# midi2trigger.net
KiCad netlist of a schematic drawn in EAGLE
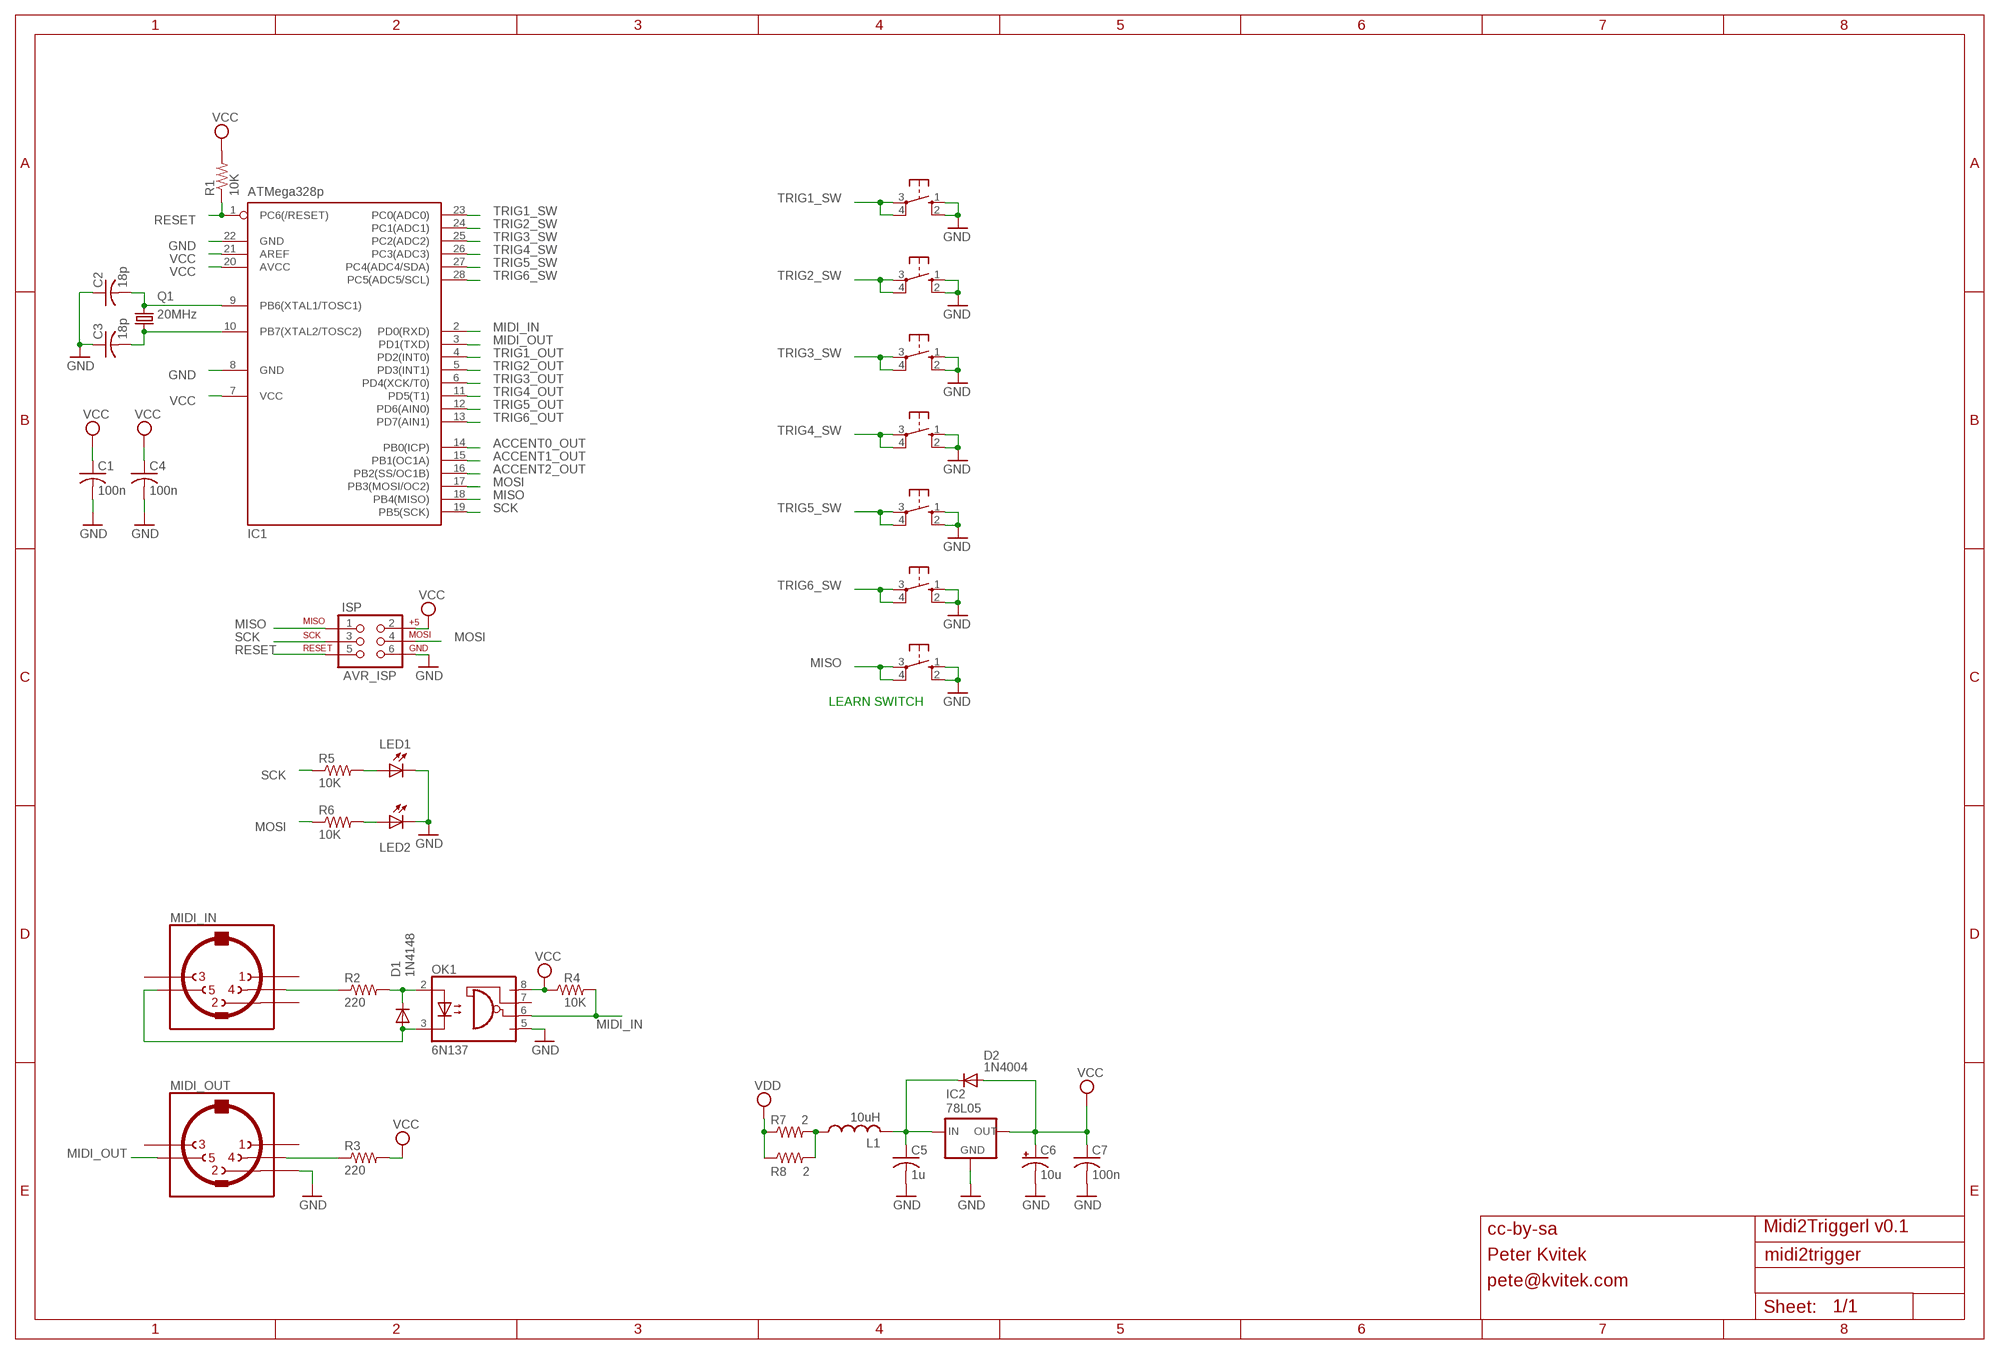
[diagram p0: schematic, sheet 1]

(export (version "E")
  (design (tool "Eeschema 10.0.6"))
  (components
    (comp (ref "C1")
      (value "100n")
      (footprint "eagle-import:C025-025X050")
      (libsource (lib "eagle-import") (part "C-US025-025X050"))
    )
    (comp (ref "C2")
      (value "18p")
      (footprint "eagle-import:C025-025X050")
      (libsource (lib "eagle-import") (part "C-US025-025X050"))
    )
    (comp (ref "C3")
      (value "18p")
      (footprint "eagle-import:C025-025X050")
      (libsource (lib "eagle-import") (part "C-US025-025X050"))
    )
    (comp (ref "C4")
      (value "100n")
      (footprint "eagle-import:C025-025X050")
      (libsource (lib "eagle-import") (part "C-US025-025X050"))
    )
    (comp (ref "C5")
      (value "1u")
      (footprint "eagle-import:C025-025X050")
      (libsource (lib "eagle-import") (part "C-US025-025X050"))
    )
    (comp (ref "C6")
      (value "10u")
      (footprint "eagle-import:E2,5-5")
      (libsource (lib "eagle-import") (part "CPOL-USE2.5-5"))
    )
    (comp (ref "C7")
      (value "100n")
      (footprint "eagle-import:C025-025X050")
      (libsource (lib "eagle-import") (part "C-US025-025X050"))
    )
    (comp (ref "D1")
      (value "1N4148")
      (footprint "eagle-import:D-5")
      (libsource (lib "eagle-import") (part "DIODE-D-5"))
    )
    (comp (ref "D2")
      (value "1N4004")
      (footprint "eagle-import:DO41-10")
      (libsource (lib "eagle-import") (part "1N4004"))
    )
    (comp (ref "IC1")
      (value "ATMega328p")
      (footprint "eagle-import:DIL28-3")
      (libsource (lib "eagle-import") (part "MEGA8-P"))
    )
    (comp (ref "IC2")
      (value "78L05")
      (footprint "eagle-import:78LXX")
      (libsource (lib "eagle-import") (part "78LXX"))
    )
    (comp (ref "ISP")
      (value "AVR_ISP")
      (footprint "eagle-import:2X3")
      (libsource (lib "eagle-import") (part "AVR_SPI_PRG_6PTH"))
    )
    (comp (ref "L1")
      (value "10uH")
      (footprint "eagle-import:0207_10")
      (libsource (lib "eagle-import") (part "L-US0207/10"))
    )
    (comp (ref "LED1")
      (value "LED3MM")
      (footprint "eagle-import:LED3MM")
      (libsource (lib "eagle-import") (part "LED3MM"))
    )
    (comp (ref "LED2")
      (value "LED3MM")
      (footprint "eagle-import:LED3MM")
      (libsource (lib "eagle-import") (part "LED3MM"))
    )
    (comp (ref "MIDI_IN")
      (value "MAB5SH")
      (footprint "eagle-import:MAB5SH")
      (libsource (lib "eagle-import") (part "MAB5SH"))
    )
    (comp (ref "MIDI_OUT")
      (value "MAB5SH")
      (footprint "eagle-import:MAB5SH")
      (libsource (lib "eagle-import") (part "MAB5SH"))
    )
    (comp (ref "OK1")
      (value "6N137")
      (footprint "eagle-import:DIL08")
      (libsource (lib "eagle-import") (part "6N137"))
    )
    (comp (ref "Q1")
      (value "20MHz")
      (footprint "eagle-import:HC49U-V")
      (libsource (lib "eagle-import") (part "CRYSTALHC49U-V"))
    )
    (comp (ref "R1")
      (value "10K")
      (footprint "eagle-import:0204_7")
      (libsource (lib "eagle-import") (part "R-US_0204/7"))
    )
    (comp (ref "R2")
      (value "220")
      (footprint "eagle-import:0204_7")
      (libsource (lib "eagle-import") (part "R-US_0204/7"))
    )
    (comp (ref "R3")
      (value "220")
      (footprint "eagle-import:0204_7")
      (libsource (lib "eagle-import") (part "R-US_0204/7"))
    )
    (comp (ref "R4")
      (value "10K")
      (footprint "eagle-import:0204_7")
      (libsource (lib "eagle-import") (part "R-US_0204/7"))
    )
    (comp (ref "R5")
      (value "10K")
      (footprint "eagle-import:0204_7")
      (libsource (lib "eagle-import") (part "R-US_0204/7"))
    )
    (comp (ref "R6")
      (value "10K")
      (footprint "eagle-import:0204_7")
      (libsource (lib "eagle-import") (part "R-US_0204/7"))
    )
    (comp (ref "R7")
      (value "2")
      (footprint "eagle-import:0204_7")
      (libsource (lib "eagle-import") (part "R-US_0204/7"))
    )
    (comp (ref "R8")
      (value "2")
      (footprint "eagle-import:0204_7")
      (libsource (lib "eagle-import") (part "R-US_0204/7"))
    )
    (comp (ref "SW1")
      (value "40-XX")
      (footprint "eagle-import:B3F-40XX")
      (libsource (lib "eagle-import") (part "40-XX"))
    )
    (comp (ref "SW2")
      (value "40-XX")
      (footprint "eagle-import:B3F-40XX")
      (libsource (lib "eagle-import") (part "40-XX"))
    )
    (comp (ref "SW3")
      (value "40-XX")
      (footprint "eagle-import:B3F-40XX")
      (libsource (lib "eagle-import") (part "40-XX"))
    )
    (comp (ref "SW4")
      (value "40-XX")
      (footprint "eagle-import:B3F-40XX")
      (libsource (lib "eagle-import") (part "40-XX"))
    )
    (comp (ref "SW5")
      (value "40-XX")
      (footprint "eagle-import:B3F-40XX")
      (libsource (lib "eagle-import") (part "40-XX"))
    )
    (comp (ref "SW6")
      (value "40-XX")
      (footprint "eagle-import:B3F-40XX")
      (libsource (lib "eagle-import") (part "40-XX"))
    )
    (comp (ref "SW7")
      (value "40-XX")
      (footprint "eagle-import:B3F-40XX")
      (libsource (lib "eagle-import") (part "40-XX"))
    )
  )
  (nets
    (net (code "1") (name "/ACCENT0_OUT") (class "Default")
      (node (ref "IC1") (pin "14") (pinfunction "PB0(ICP)_14") (pintype "bidirectional"))
    )
    (net (code "2") (name "/ACCENT1_OUT") (class "Default")
      (node (ref "IC1") (pin "15") (pinfunction "PB1(OC1A)_15") (pintype "bidirectional"))
    )
    (net (code "3") (name "/ACCENT2_OUT") (class "Default")
      (node (ref "IC1") (pin "16") (pinfunction "PB2(SS/OC1B)_16") (pintype "bidirectional"))
    )
    (net (code "4") (name "/MIDI_IN") (class "Default")
      (node (ref "IC1") (pin "2") (pinfunction "PD0(RXD)_2") (pintype "bidirectional"))
      (node (ref "OK1") (pin "6") (pinfunction "VO_6") (pintype "passive"))
      (node (ref "R4") (pin "2") (pinfunction "2_2") (pintype "passive"))
    )
    (net (code "5") (name "/MIDI_OUT") (class "Default")
      (node (ref "IC1") (pin "3") (pinfunction "PD1(TXD)_3") (pintype "bidirectional"))
      (node (ref "MIDI_OUT") (pin "5") (pinfunction "5_5") (pintype "passive"))
    )
    (net (code "6") (name "/MISO") (class "Default")
      (node (ref "IC1") (pin "18") (pinfunction "PB4(MISO)_18") (pintype "bidirectional"))
      (node (ref "ISP") (pin "1") (pinfunction "1_1") (pintype "passive"))
      (node (ref "SW7") (pin "3") (pinfunction "P_3") (pintype "passive"))
      (node (ref "SW7") (pin "4") (pinfunction "P1_4") (pintype "passive"))
    )
    (net (code "7") (name "/MOSI") (class "Default")
      (node (ref "IC1") (pin "17") (pinfunction "PB3(MOSI/OC2)_17") (pintype "bidirectional"))
      (node (ref "ISP") (pin "4") (pinfunction "4_4") (pintype "passive"))
      (node (ref "R6") (pin "1") (pinfunction "1_1") (pintype "passive"))
    )
    (net (code "8") (name "/RESET") (class "Default")
      (node (ref "IC1") (pin "1") (pinfunction "PC6(/RESET)_1") (pintype "bidirectional"))
      (node (ref "ISP") (pin "5") (pinfunction "5_5") (pintype "passive"))
      (node (ref "R1") (pin "1") (pinfunction "1_1") (pintype "passive"))
    )
    (net (code "9") (name "/SCK") (class "Default")
      (node (ref "IC1") (pin "19") (pinfunction "PB5(SCK)_19") (pintype "bidirectional"))
      (node (ref "ISP") (pin "3") (pinfunction "3_3") (pintype "passive"))
      (node (ref "R5") (pin "1") (pinfunction "1_1") (pintype "passive"))
    )
    (net (code "10") (name "/TRIG1_OUT") (class "Default")
      (node (ref "IC1") (pin "4") (pinfunction "PD2(INT0)_4") (pintype "bidirectional"))
    )
    (net (code "11") (name "/TRIG1_SW") (class "Default")
      (node (ref "IC1") (pin "23") (pinfunction "PC0(ADC0)_23") (pintype "bidirectional"))
      (node (ref "SW1") (pin "3") (pinfunction "P_3") (pintype "passive"))
      (node (ref "SW1") (pin "4") (pinfunction "P1_4") (pintype "passive"))
    )
    (net (code "12") (name "/TRIG2_OUT") (class "Default")
      (node (ref "IC1") (pin "5") (pinfunction "PD3(INT1)_5") (pintype "bidirectional"))
    )
    (net (code "13") (name "/TRIG2_SW") (class "Default")
      (node (ref "IC1") (pin "24") (pinfunction "PC1(ADC1)_24") (pintype "bidirectional"))
      (node (ref "SW2") (pin "3") (pinfunction "P_3") (pintype "passive"))
      (node (ref "SW2") (pin "4") (pinfunction "P1_4") (pintype "passive"))
    )
    (net (code "14") (name "/TRIG3_OUT") (class "Default")
      (node (ref "IC1") (pin "6") (pinfunction "PD4(XCK/T0)_6") (pintype "bidirectional"))
    )
    (net (code "15") (name "/TRIG3_SW") (class "Default")
      (node (ref "IC1") (pin "25") (pinfunction "PC2(ADC2)_25") (pintype "bidirectional"))
      (node (ref "SW3") (pin "3") (pinfunction "P_3") (pintype "passive"))
      (node (ref "SW3") (pin "4") (pinfunction "P1_4") (pintype "passive"))
    )
    (net (code "16") (name "/TRIG4_OUT") (class "Default")
      (node (ref "IC1") (pin "11") (pinfunction "PD5(T1)_11") (pintype "bidirectional"))
    )
    (net (code "17") (name "/TRIG4_SW") (class "Default")
      (node (ref "IC1") (pin "26") (pinfunction "PC3(ADC3)_26") (pintype "bidirectional"))
      (node (ref "SW4") (pin "3") (pinfunction "P_3") (pintype "passive"))
      (node (ref "SW4") (pin "4") (pinfunction "P1_4") (pintype "passive"))
    )
    (net (code "18") (name "/TRIG5_OUT") (class "Default")
      (node (ref "IC1") (pin "12") (pinfunction "PD6(AIN0)_12") (pintype "bidirectional"))
    )
    (net (code "19") (name "/TRIG5_SW") (class "Default")
      (node (ref "IC1") (pin "27") (pinfunction "PC4(ADC4/SDA)_27") (pintype "bidirectional"))
      (node (ref "SW5") (pin "3") (pinfunction "P_3") (pintype "passive"))
      (node (ref "SW5") (pin "4") (pinfunction "P1_4") (pintype "passive"))
    )
    (net (code "20") (name "/TRIG6_OUT") (class "Default")
      (node (ref "IC1") (pin "13") (pinfunction "PD7(AIN1)_13") (pintype "bidirectional"))
    )
    (net (code "21") (name "/TRIG6_SW") (class "Default")
      (node (ref "IC1") (pin "28") (pinfunction "PC5(ADC5/SCL)_28") (pintype "bidirectional"))
      (node (ref "SW6") (pin "3") (pinfunction "P_3") (pintype "passive"))
      (node (ref "SW6") (pin "4") (pinfunction "P1_4") (pintype "passive"))
    )
    (net (code "22") (name "GND") (class "Default")
      (node (ref "C1") (pin "2") (pinfunction "2_2") (pintype "passive"))
      (node (ref "C2") (pin "1") (pinfunction "1_1") (pintype "passive"))
      (node (ref "C3") (pin "1") (pinfunction "1_1") (pintype "passive"))
      (node (ref "C4") (pin "2") (pinfunction "2_2") (pintype "passive"))
      (node (ref "C5") (pin "2") (pinfunction "2_2") (pintype "passive"))
      (node (ref "C6") (pin "-") (pinfunction "-_-") (pintype "passive"))
      (node (ref "C7") (pin "2") (pinfunction "2_2") (pintype "passive"))
      (node (ref "IC1") (pin "22") (pinfunction "GND_22") (pintype "power_in"))
      (node (ref "IC1") (pin "8") (pinfunction "GND_8") (pintype "power_in"))
      (node (ref "IC2") (pin "GND") (pinfunction "GND_GND") (pintype "input"))
      (node (ref "ISP") (pin "6") (pinfunction "6_6") (pintype "passive"))
      (node (ref "LED1") (pin "K") (pinfunction "C_K") (pintype "passive"))
      (node (ref "LED2") (pin "K") (pinfunction "C_K") (pintype "passive"))
      (node (ref "MIDI_OUT") (pin "2") (pinfunction "2_2") (pintype "passive"))
      (node (ref "OK1") (pin "5") (pinfunction "GND_5") (pintype "passive"))
      (node (ref "SW1") (pin "1") (pinfunction "S_1") (pintype "passive"))
      (node (ref "SW1") (pin "2") (pinfunction "S1_2") (pintype "passive"))
      (node (ref "SW2") (pin "1") (pinfunction "S_1") (pintype "passive"))
      (node (ref "SW2") (pin "2") (pinfunction "S1_2") (pintype "passive"))
      (node (ref "SW3") (pin "1") (pinfunction "S_1") (pintype "passive"))
      (node (ref "SW3") (pin "2") (pinfunction "S1_2") (pintype "passive"))
      (node (ref "SW4") (pin "1") (pinfunction "S_1") (pintype "passive"))
      (node (ref "SW4") (pin "2") (pinfunction "S1_2") (pintype "passive"))
      (node (ref "SW5") (pin "1") (pinfunction "S_1") (pintype "passive"))
      (node (ref "SW5") (pin "2") (pinfunction "S1_2") (pintype "passive"))
      (node (ref "SW6") (pin "1") (pinfunction "S_1") (pintype "passive"))
      (node (ref "SW6") (pin "2") (pinfunction "S1_2") (pintype "passive"))
      (node (ref "SW7") (pin "1") (pinfunction "S_1") (pintype "passive"))
      (node (ref "SW7") (pin "2") (pinfunction "S1_2") (pintype "passive"))
    )
    (net (code "23") (name "Net-(C5-Pad1)") (class "Default")
      (node (ref "C5") (pin "1") (pinfunction "1_1") (pintype "passive"))
      (node (ref "D2") (pin "C") (pinfunction "C_C") (pintype "passive"))
      (node (ref "IC2") (pin "IN") (pinfunction "IN_IN") (pintype "input"))
      (node (ref "L1") (pin "2") (pinfunction "2_2") (pintype "passive"))
    )
    (net (code "24") (name "Net-(IC1-PB6(XTAL1{slash}TOSC1))") (class "Default")
      (node (ref "C2") (pin "2") (pinfunction "2_2") (pintype "passive"))
      (node (ref "IC1") (pin "9") (pinfunction "PB6(XTAL1/TOSC1)_9") (pintype "bidirectional"))
      (node (ref "Q1") (pin "2") (pinfunction "2_2") (pintype "passive"))
    )
    (net (code "25") (name "Net-(IC1-PB7(XTAL2{slash}TOSC2))") (class "Default")
      (node (ref "C3") (pin "2") (pinfunction "2_2") (pintype "passive"))
      (node (ref "IC1") (pin "10") (pinfunction "PB7(XTAL2/TOSC2)_10") (pintype "bidirectional"))
      (node (ref "Q1") (pin "1") (pinfunction "1_1") (pintype "passive"))
    )
    (net (code "26") (name "Net-(L1-Pad1)") (class "Default")
      (node (ref "L1") (pin "1") (pinfunction "1_1") (pintype "passive"))
      (node (ref "R7") (pin "2") (pinfunction "2_2") (pintype "passive"))
      (node (ref "R8") (pin "2") (pinfunction "2_2") (pintype "passive"))
    )
    (net (code "27") (name "Net-(LED1-PadA)") (class "Default")
      (node (ref "LED1") (pin "A") (pinfunction "A_A") (pintype "passive"))
      (node (ref "R5") (pin "2") (pinfunction "2_2") (pintype "passive"))
    )
    (net (code "28") (name "Net-(LED2-PadA)") (class "Default")
      (node (ref "LED2") (pin "A") (pinfunction "A_A") (pintype "passive"))
      (node (ref "R6") (pin "2") (pinfunction "2_2") (pintype "passive"))
    )
    (net (code "29") (name "Net-(MIDI_IN-Pad4)") (class "Default")
      (node (ref "MIDI_IN") (pin "4") (pinfunction "4_4") (pintype "passive"))
      (node (ref "R2") (pin "1") (pinfunction "1_1") (pintype "passive"))
    )
    (net (code "30") (name "Net-(MIDI_OUT-Pad4)") (class "Default")
      (node (ref "MIDI_OUT") (pin "4") (pinfunction "4_4") (pintype "passive"))
      (node (ref "R3") (pin "1") (pinfunction "1_1") (pintype "passive"))
    )
    (net (code "31") (name "Net-(OK1-A)") (class "Default")
      (node (ref "D1") (pin "C") (pinfunction "C_C") (pintype "passive"))
      (node (ref "OK1") (pin "2") (pinfunction "A_2") (pintype "passive"))
      (node (ref "R2") (pin "2") (pinfunction "2_2") (pintype "passive"))
    )
    (net (code "32") (name "Net-(OK1-C)") (class "Default")
      (node (ref "D1") (pin "A") (pinfunction "A_A") (pintype "passive"))
      (node (ref "MIDI_IN") (pin "5") (pinfunction "5_5") (pintype "passive"))
      (node (ref "OK1") (pin "3") (pinfunction "C_3") (pintype "passive"))
    )
    (net (code "33") (name "VCC") (class "Default")
      (node (ref "C1") (pin "1") (pinfunction "1_1") (pintype "passive"))
      (node (ref "C4") (pin "1") (pinfunction "1_1") (pintype "passive"))
      (node (ref "C6") (pin "+") (pinfunction "+_+") (pintype "passive"))
      (node (ref "C7") (pin "1") (pinfunction "1_1") (pintype "passive"))
      (node (ref "D2") (pin "A") (pinfunction "A_A") (pintype "passive"))
      (node (ref "IC1") (pin "20") (pinfunction "AVCC_20") (pintype "power_in"))
      (node (ref "IC1") (pin "21") (pinfunction "AREF_21") (pintype "passive"))
      (node (ref "IC1") (pin "7") (pinfunction "VCC_7") (pintype "power_in"))
      (node (ref "IC2") (pin "OUT") (pinfunction "OUT_OUT") (pintype "passive"))
      (node (ref "ISP") (pin "2") (pinfunction "2_2") (pintype "passive"))
      (node (ref "OK1") (pin "8") (pinfunction "VCC_8") (pintype "passive"))
      (node (ref "R1") (pin "2") (pinfunction "2_2") (pintype "passive"))
      (node (ref "R3") (pin "2") (pinfunction "2_2") (pintype "passive"))
      (node (ref "R4") (pin "1") (pinfunction "1_1") (pintype "passive"))
    )
    (net (code "34") (name "VDD") (class "Default")
      (node (ref "R7") (pin "1") (pinfunction "1_1") (pintype "passive"))
      (node (ref "R8") (pin "1") (pinfunction "1_1") (pintype "passive"))
    )
    (net (code "35") (name "unconnected-(MIDI_IN-Pad1)") (class "Default")
      (node (ref "MIDI_IN") (pin "1") (pinfunction "1_1") (pintype "passive"))
    )
    (net (code "36") (name "unconnected-(MIDI_IN-Pad2)") (class "Default")
      (node (ref "MIDI_IN") (pin "2") (pinfunction "2_2") (pintype "passive"))
    )
    (net (code "37") (name "unconnected-(MIDI_IN-Pad3)") (class "Default")
      (node (ref "MIDI_IN") (pin "3") (pinfunction "3_3") (pintype "passive"))
    )
    (net (code "38") (name "unconnected-(MIDI_OUT-Pad1)") (class "Default")
      (node (ref "MIDI_OUT") (pin "1") (pinfunction "1_1") (pintype "passive"))
    )
    (net (code "39") (name "unconnected-(MIDI_OUT-Pad3)") (class "Default")
      (node (ref "MIDI_OUT") (pin "3") (pinfunction "3_3") (pintype "passive"))
    )
    (net (code "40") (name "unconnected-(OK1-VE-Pad7)") (class "Default")
      (node (ref "OK1") (pin "7") (pinfunction "VE_7") (pintype "passive"))
    )
  )
)
